# MasterMind_dll.net
KiCad netlist of a schematic drawn in EAGLE
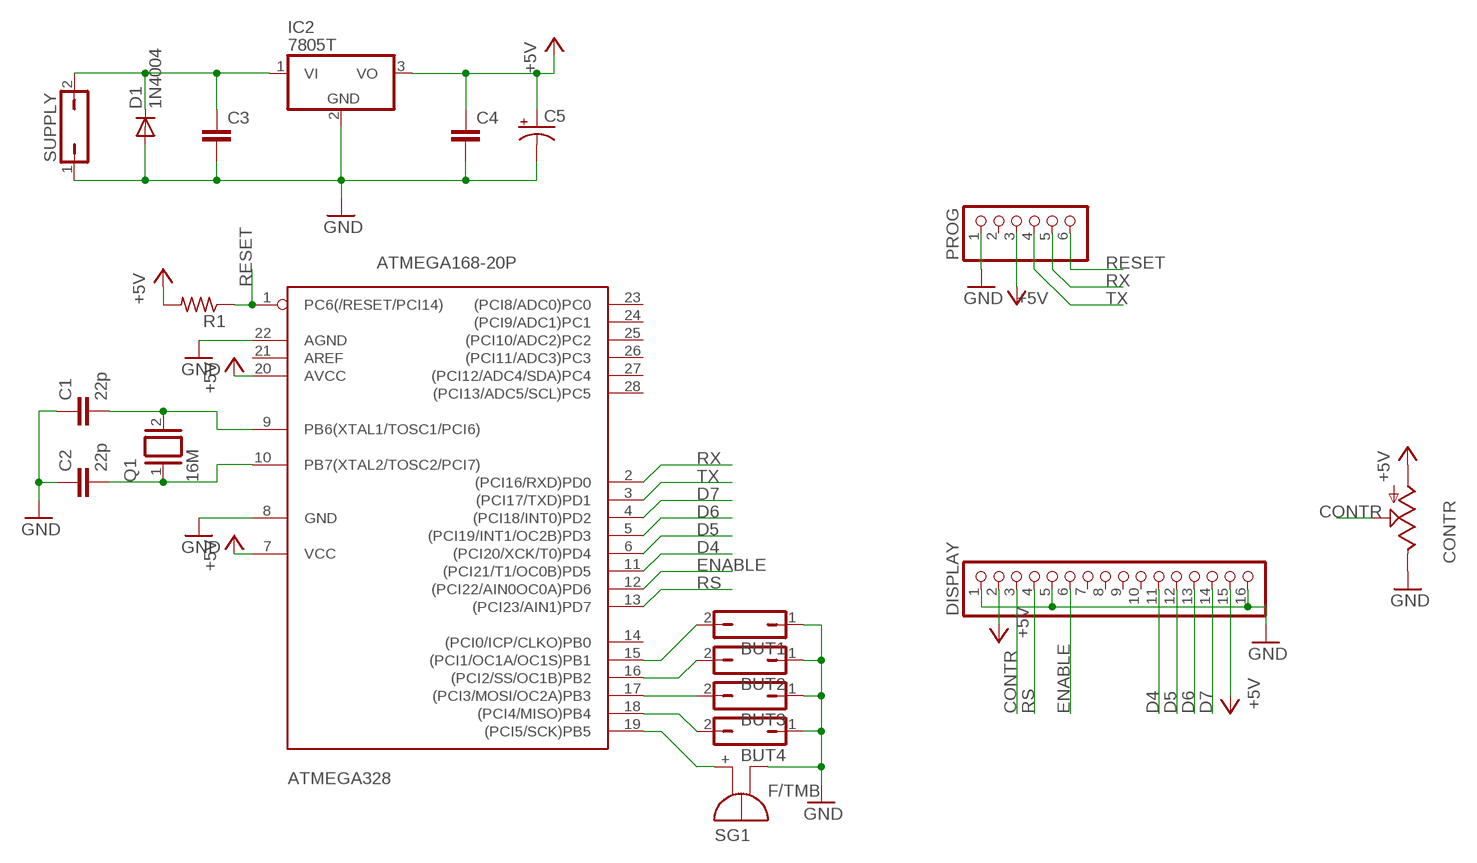
[diagram p0: schematic, sheet 1]

(export (version "E")
  (design (tool "Eeschema 10.0.6"))
  (components
    (comp (ref "ATMEGA328")
      (value "ATMEGA168-20P")
      (footprint "eagle-import:DIL28-3")
      (libsource (lib "eagle-import") (part "ATMEGA168P-20"))
    )
    (comp (ref "BUT1")
      (value "JP1Q")
      (footprint "eagle-import:JP1")
      (libsource (lib "eagle-import") (part "JP1Q"))
    )
    (comp (ref "BUT2")
      (value "JP1Q")
      (footprint "eagle-import:JP1")
      (libsource (lib "eagle-import") (part "JP1Q"))
    )
    (comp (ref "BUT3")
      (value "JP1Q")
      (footprint "eagle-import:JP1")
      (libsource (lib "eagle-import") (part "JP1Q"))
    )
    (comp (ref "BUT4")
      (value "JP1Q")
      (footprint "eagle-import:JP1")
      (libsource (lib "eagle-import") (part "JP1Q"))
    )
    (comp (ref "C1")
      (value "22p")
      (footprint "eagle-import:C025-024X044")
      (libsource (lib "eagle-import") (part "resistor_C-EU025-024X044"))
    )
    (comp (ref "C2")
      (value "22p")
      (footprint "eagle-import:C025-024X044")
      (libsource (lib "eagle-import") (part "resistor_C-EU025-024X044"))
    )
    (comp (ref "C3")
      (value "C-EU050-025X075")
      (footprint "eagle-import:C050-025X075")
      (libsource (lib "eagle-import") (part "C-EU050-025X075"))
    )
    (comp (ref "C4")
      (value "C-EU050-025X075")
      (footprint "eagle-import:C050-025X075")
      (libsource (lib "eagle-import") (part "C-EU050-025X075"))
    )
    (comp (ref "C5")
      (value "CPOL-USE2,5-6E")
      (footprint "eagle-import:E2,5-6E")
      (libsource (lib "eagle-import") (part "CPOL-USE2,5-6E"))
    )
    (comp (ref "CONTR")
      (value "TRIM_US-B64Y")
      (footprint "eagle-import:B64Y")
      (libsource (lib "eagle-import") (part "TRIM_US-B64Y"))
    )
    (comp (ref "D1")
      (value "1N4004")
      (footprint "eagle-import:DO41-10")
      (libsource (lib "eagle-import") (part "1N4004"))
    )
    (comp (ref "DISPLAY")
      (value "PINHD-1X16")
      (footprint "eagle-import:1X16")
      (libsource (lib "eagle-import") (part "PINHD-1X16"))
    )
    (comp (ref "IC2")
      (value "7805T")
      (footprint "eagle-import:TO220H")
      (libsource (lib "eagle-import") (part "78T05"))
    )
    (comp (ref "PROG")
      (value "PINHD-1X6/90")
      (footprint "eagle-import:1X06_90")
      (libsource (lib "eagle-import") (part "PINHD-1X6/90"))
    )
    (comp (ref "Q1")
      (value "16M")
      (footprint "eagle-import:QS")
      (libsource (lib "eagle-import") (part "XTAL/S"))
    )
    (comp (ref "R1")
      (value "R-US_0204/7")
      (footprint "eagle-import:0204_7")
      (libsource (lib "eagle-import") (part "R-US_0204/7"))
    )
    (comp (ref "SG1")
      (value "F/TMB")
      (footprint "eagle-import:F_TMB")
      (libsource (lib "eagle-import") (part "F/TMB"))
    )
    (comp (ref "SUPPLY")
      (value "JP1Q")
      (footprint "eagle-import:JP1")
      (libsource (lib "eagle-import") (part "JP1Q"))
    )
  )
  (nets
    (net (code "1") (name "+5V") (class "Default")
      (node (ref "ATMEGA328") (pin "20") (pinfunction "AVCC_20") (pintype "bidirectional"))
      (node (ref "ATMEGA328") (pin "7") (pinfunction "VCC_7") (pintype "bidirectional"))
      (node (ref "C4") (pin "1") (pinfunction "1_1") (pintype "passive"))
      (node (ref "C5") (pin "+") (pinfunction "+_+") (pintype "passive"))
      (node (ref "CONTR") (pin "A") (pinfunction "A_A") (pintype "passive"))
      (node (ref "DISPLAY") (pin "15") (pinfunction "15_15") (pintype "passive"))
      (node (ref "DISPLAY") (pin "2") (pinfunction "2_2") (pintype "passive"))
      (node (ref "IC2") (pin "3") (pinfunction "VO_3") (pintype "passive"))
      (node (ref "PROG") (pin "3") (pinfunction "3_3") (pintype "passive"))
      (node (ref "R1") (pin "2") (pinfunction "2_2") (pintype "passive"))
    )
    (net (code "2") (name "/CONTR") (class "Default")
      (node (ref "CONTR") (pin "S") (pinfunction "S_S") (pintype "passive"))
      (node (ref "DISPLAY") (pin "3") (pinfunction "3_3") (pintype "passive"))
    )
    (net (code "3") (name "/D4") (class "Default")
      (node (ref "ATMEGA328") (pin "11") (pinfunction "(PCI21/T1/OC0B)PD5_11") (pintype "bidirectional"))
      (node (ref "DISPLAY") (pin "11") (pinfunction "11_11") (pintype "passive"))
    )
    (net (code "4") (name "/D5") (class "Default")
      (node (ref "ATMEGA328") (pin "6") (pinfunction "(PCI20/XCK/T0)PD4_6") (pintype "bidirectional"))
      (node (ref "DISPLAY") (pin "12") (pinfunction "12_12") (pintype "passive"))
    )
    (net (code "5") (name "/D6") (class "Default")
      (node (ref "ATMEGA328") (pin "5") (pinfunction "(PCI19/INT1/OC2B)PD3_5") (pintype "bidirectional"))
      (node (ref "DISPLAY") (pin "13") (pinfunction "13_13") (pintype "passive"))
    )
    (net (code "6") (name "/D7") (class "Default")
      (node (ref "ATMEGA328") (pin "4") (pinfunction "(PCI18/INT0)PD2_4") (pintype "bidirectional"))
      (node (ref "DISPLAY") (pin "14") (pinfunction "14_14") (pintype "passive"))
    )
    (net (code "7") (name "/ENABLE") (class "Default")
      (node (ref "ATMEGA328") (pin "12") (pinfunction "(PCI22/AIN0OC0A)PD6_12") (pintype "bidirectional"))
      (node (ref "DISPLAY") (pin "6") (pinfunction "6_6") (pintype "passive"))
    )
    (net (code "8") (name "/RESET") (class "Default")
      (node (ref "ATMEGA328") (pin "1") (pinfunction "PC6(/RESET/PCI14)_1") (pintype "bidirectional"))
      (node (ref "PROG") (pin "6") (pinfunction "6_6") (pintype "passive"))
      (node (ref "R1") (pin "1") (pinfunction "1_1") (pintype "passive"))
    )
    (net (code "9") (name "/RS") (class "Default")
      (node (ref "ATMEGA328") (pin "13") (pinfunction "(PCI23/AIN1)PD7_13") (pintype "bidirectional"))
      (node (ref "DISPLAY") (pin "4") (pinfunction "4_4") (pintype "passive"))
    )
    (net (code "10") (name "/RX") (class "Default")
      (node (ref "ATMEGA328") (pin "2") (pinfunction "(PCI16/RXD)PD0_2") (pintype "bidirectional"))
      (node (ref "PROG") (pin "5") (pinfunction "5_5") (pintype "passive"))
    )
    (net (code "11") (name "/TX") (class "Default")
      (node (ref "ATMEGA328") (pin "3") (pinfunction "(PCI17/TXD)PD1_3") (pintype "bidirectional"))
      (node (ref "PROG") (pin "4") (pinfunction "4_4") (pintype "passive"))
    )
    (net (code "12") (name "GND") (class "Default")
      (node (ref "ATMEGA328") (pin "22") (pinfunction "AGND_22") (pintype "bidirectional"))
      (node (ref "ATMEGA328") (pin "8") (pinfunction "GND_8") (pintype "bidirectional"))
      (node (ref "BUT1") (pin "1") (pinfunction "1_1") (pintype "passive"))
      (node (ref "BUT2") (pin "1") (pinfunction "1_1") (pintype "passive"))
      (node (ref "BUT3") (pin "1") (pinfunction "1_1") (pintype "passive"))
      (node (ref "BUT4") (pin "1") (pinfunction "1_1") (pintype "passive"))
      (node (ref "C1") (pin "1") (pinfunction "1_1") (pintype "passive"))
      (node (ref "C2") (pin "1") (pinfunction "1_1") (pintype "passive"))
      (node (ref "C3") (pin "2") (pinfunction "2_2") (pintype "passive"))
      (node (ref "C4") (pin "2") (pinfunction "2_2") (pintype "passive"))
      (node (ref "C5") (pin "-") (pinfunction "-_-") (pintype "passive"))
      (node (ref "CONTR") (pin "E") (pinfunction "E_E") (pintype "passive"))
      (node (ref "D1") (pin "A") (pinfunction "A_A") (pintype "passive"))
      (node (ref "DISPLAY") (pin "1") (pinfunction "1_1") (pintype "passive"))
      (node (ref "DISPLAY") (pin "16") (pinfunction "16_16") (pintype "passive"))
      (node (ref "DISPLAY") (pin "5") (pinfunction "5_5") (pintype "passive"))
      (node (ref "IC2") (pin "2") (pinfunction "GND_2") (pintype "passive"))
      (node (ref "PROG") (pin "1") (pinfunction "1_1") (pintype "passive"))
      (node (ref "SG1") (pin "-") (pinfunction "-_-") (pintype "passive"))
      (node (ref "SUPPLY") (pin "1") (pinfunction "1_1") (pintype "passive"))
    )
    (net (code "13") (name "Net-(ATMEGA328-(PCI1{slash}OC1A{slash}OC1S)PB1)") (class "Default")
      (node (ref "ATMEGA328") (pin "15") (pinfunction "(PCI1/OC1A/OC1S)PB1_15") (pintype "bidirectional"))
      (node (ref "BUT1") (pin "2") (pinfunction "2_2") (pintype "passive"))
    )
    (net (code "14") (name "Net-(ATMEGA328-(PCI2{slash}SS{slash}OC1B)PB2)") (class "Default")
      (node (ref "ATMEGA328") (pin "16") (pinfunction "(PCI2/SS/OC1B)PB2_16") (pintype "bidirectional"))
      (node (ref "BUT2") (pin "2") (pinfunction "2_2") (pintype "passive"))
    )
    (net (code "15") (name "Net-(ATMEGA328-(PCI3{slash}MOSI{slash}OC2A)PB3)") (class "Default")
      (node (ref "ATMEGA328") (pin "17") (pinfunction "(PCI3/MOSI/OC2A)PB3_17") (pintype "bidirectional"))
      (node (ref "BUT3") (pin "2") (pinfunction "2_2") (pintype "passive"))
    )
    (net (code "16") (name "Net-(ATMEGA328-(PCI4{slash}MISO)PB4)") (class "Default")
      (node (ref "ATMEGA328") (pin "18") (pinfunction "(PCI4/MISO)PB4_18") (pintype "bidirectional"))
      (node (ref "BUT4") (pin "2") (pinfunction "2_2") (pintype "passive"))
    )
    (net (code "17") (name "Net-(ATMEGA328-(PCI5{slash}SCK)PB5)") (class "Default")
      (node (ref "ATMEGA328") (pin "19") (pinfunction "(PCI5/SCK)PB5_19") (pintype "bidirectional"))
      (node (ref "SG1") (pin "+") (pinfunction "+_+") (pintype "passive"))
    )
    (net (code "18") (name "Net-(ATMEGA328-PB6(XTAL1{slash}TOSC1{slash}PCI6))") (class "Default")
      (node (ref "ATMEGA328") (pin "9") (pinfunction "PB6(XTAL1/TOSC1/PCI6)_9") (pintype "bidirectional"))
      (node (ref "C1") (pin "2") (pinfunction "2_2") (pintype "passive"))
      (node (ref "Q1") (pin "2") (pinfunction "2_2") (pintype "passive"))
    )
    (net (code "19") (name "Net-(ATMEGA328-PB7(XTAL2{slash}TOSC2{slash}PCI7))") (class "Default")
      (node (ref "ATMEGA328") (pin "10") (pinfunction "PB7(XTAL2/TOSC2/PCI7)_10") (pintype "bidirectional"))
      (node (ref "C2") (pin "2") (pinfunction "2_2") (pintype "passive"))
      (node (ref "Q1") (pin "1") (pinfunction "1_1") (pintype "passive"))
    )
    (net (code "20") (name "Net-(IC2-VI)") (class "Default")
      (node (ref "C3") (pin "1") (pinfunction "1_1") (pintype "passive"))
      (node (ref "D1") (pin "C") (pinfunction "C_C") (pintype "passive"))
      (node (ref "IC2") (pin "1") (pinfunction "VI_1") (pintype "input"))
      (node (ref "SUPPLY") (pin "2") (pinfunction "2_2") (pintype "passive"))
    )
    (net (code "21") (name "unconnected-(ATMEGA328-(PCI0{slash}ICP{slash}CLKO)PB0-Pad14)") (class "Default")
      (node (ref "ATMEGA328") (pin "14") (pinfunction "(PCI0/ICP/CLKO)PB0_14") (pintype "bidirectional"))
    )
    (net (code "22") (name "unconnected-(ATMEGA328-(PCI8{slash}ADC0)PC0-Pad23)") (class "Default")
      (node (ref "ATMEGA328") (pin "23") (pinfunction "(PCI8/ADC0)PC0_23") (pintype "bidirectional"))
    )
    (net (code "23") (name "unconnected-(ATMEGA328-(PCI9{slash}ADC1)PC1-Pad24)") (class "Default")
      (node (ref "ATMEGA328") (pin "24") (pinfunction "(PCI9/ADC1)PC1_24") (pintype "bidirectional"))
    )
    (net (code "24") (name "unconnected-(ATMEGA328-(PCI10{slash}ADC2)PC2-Pad25)") (class "Default")
      (node (ref "ATMEGA328") (pin "25") (pinfunction "(PCI10/ADC2)PC2_25") (pintype "bidirectional"))
    )
    (net (code "25") (name "unconnected-(ATMEGA328-(PCI11{slash}ADC3)PC3-Pad26)") (class "Default")
      (node (ref "ATMEGA328") (pin "26") (pinfunction "(PCI11/ADC3)PC3_26") (pintype "bidirectional"))
    )
    (net (code "26") (name "unconnected-(ATMEGA328-(PCI12{slash}ADC4{slash}SDA)PC4-Pad27)") (class "Default")
      (node (ref "ATMEGA328") (pin "27") (pinfunction "(PCI12/ADC4/SDA)PC4_27") (pintype "bidirectional"))
    )
    (net (code "27") (name "unconnected-(ATMEGA328-(PCI13{slash}ADC5{slash}SCL)PC5-Pad28)") (class "Default")
      (node (ref "ATMEGA328") (pin "28") (pinfunction "(PCI13/ADC5/SCL)PC5_28") (pintype "bidirectional"))
    )
    (net (code "28") (name "unconnected-(ATMEGA328-AREF-Pad21)") (class "Default")
      (node (ref "ATMEGA328") (pin "21") (pinfunction "AREF_21") (pintype "bidirectional"))
    )
    (net (code "29") (name "unconnected-(DISPLAY-Pad7)") (class "Default")
      (node (ref "DISPLAY") (pin "7") (pinfunction "7_7") (pintype "passive"))
    )
    (net (code "30") (name "unconnected-(DISPLAY-Pad8)") (class "Default")
      (node (ref "DISPLAY") (pin "8") (pinfunction "8_8") (pintype "passive"))
    )
    (net (code "31") (name "unconnected-(DISPLAY-Pad9)") (class "Default")
      (node (ref "DISPLAY") (pin "9") (pinfunction "9_9") (pintype "passive"))
    )
    (net (code "32") (name "unconnected-(DISPLAY-Pad10)") (class "Default")
      (node (ref "DISPLAY") (pin "10") (pinfunction "10_10") (pintype "passive"))
    )
    (net (code "33") (name "unconnected-(PROG-Pad2)") (class "Default")
      (node (ref "PROG") (pin "2") (pinfunction "2_2") (pintype "passive"))
    )
  )
)
